# M117E.net
KiCad netlist of a schematic drawn in EAGLE
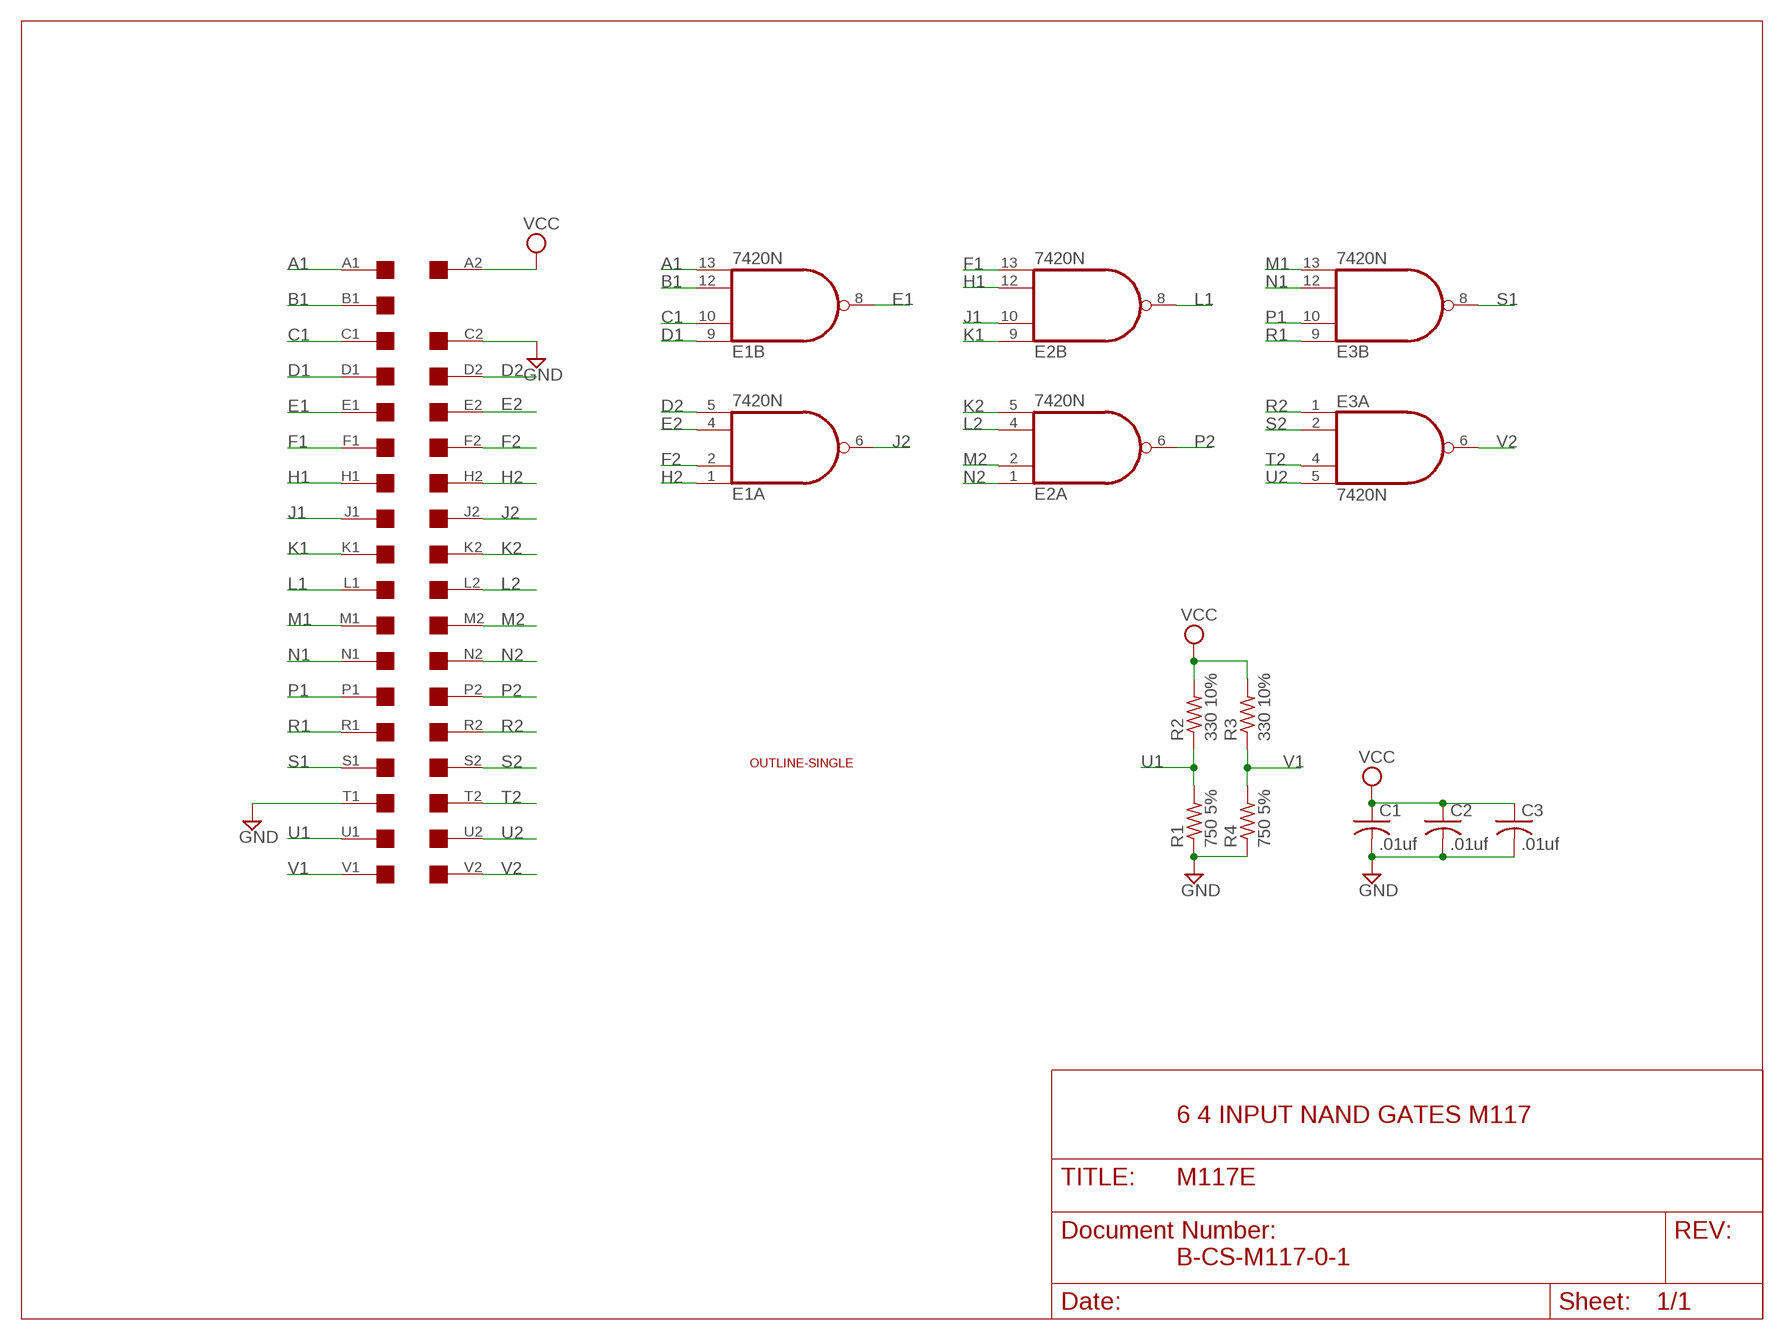
[diagram p0: schematic, sheet 1]

(export (version "E")
  (design (tool "Eeschema 10.0.6"))
  (components
    (comp (ref "C1")
      (value ".01uf")
      (footprint "eagle-import:C050-025X075")
      (libsource (lib "eagle-import") (part "C-US050-025X075"))
    )
    (comp (ref "C2")
      (value ".01uf")
      (footprint "eagle-import:C050-025X075")
      (libsource (lib "eagle-import") (part "C-US050-025X075"))
    )
    (comp (ref "C3")
      (value ".01uf")
      (footprint "eagle-import:C050-025X075")
      (libsource (lib "eagle-import") (part "C-US050-025X075"))
    )
    (comp (ref "E1")
      (value "7420N")
      (footprint "eagle-import:DIL14")
      (libsource (lib "eagle-import") (part "7420NS"))
    )
    (comp (ref "E2")
      (value "7420N")
      (footprint "eagle-import:DIL14")
      (libsource (lib "eagle-import") (part "7420NS"))
    )
    (comp (ref "E3")
      (value "7420N")
      (footprint "eagle-import:DIL14")
      (libsource (lib "eagle-import") (part "7420NS"))
    )
    (comp (ref "R1")
      (value "750 5%")
      (footprint "eagle-import:0207_10")
      (libsource (lib "eagle-import") (part "R-US_0207/10"))
    )
    (comp (ref "R2")
      (value "330 10%")
      (footprint "eagle-import:0207_10")
      (libsource (lib "eagle-import") (part "R-US_0207/10"))
    )
    (comp (ref "R3")
      (value "330 10%")
      (footprint "eagle-import:0207_10")
      (libsource (lib "eagle-import") (part "R-US_0207/10"))
    )
    (comp (ref "R4")
      (value "750 5%")
      (footprint "eagle-import:0207_10")
      (libsource (lib "eagle-import") (part "R-US_0207/10"))
    )
    (comp (ref "U$1")
      (value "SINGLE")
      (footprint "eagle-import:EDGE-CON2")
      (libsource (lib "eagle-import") (part "SINGLE"))
    )
    (comp (ref "U$4")
      (value "OUTLINE-SINGLE")
      (footprint "eagle-import:SINGLE")
      (libsource (lib "eagle-import") (part "OUTLINE-SINGLE"))
    )
  )
  (nets
    (net (code "1") (name "/A1") (class "Default")
      (node (ref "E1") (pin "13") (pinfunction "I3_13") (pintype "input"))
      (node (ref "U$1") (pin "A1") (pinfunction "1_A1") (pintype "bidirectional"))
    )
    (net (code "2") (name "/B1") (class "Default")
      (node (ref "E1") (pin "12") (pinfunction "I2_12") (pintype "input"))
      (node (ref "U$1") (pin "B1") (pinfunction "1_B1") (pintype "bidirectional"))
    )
    (net (code "3") (name "/C1") (class "Default")
      (node (ref "E1") (pin "10") (pinfunction "I1_10") (pintype "input"))
      (node (ref "U$1") (pin "C1") (pinfunction "1_C1") (pintype "bidirectional"))
    )
    (net (code "4") (name "/D1") (class "Default")
      (node (ref "E1") (pin "9") (pinfunction "I0_9") (pintype "input"))
      (node (ref "U$1") (pin "D1") (pinfunction "1_D1") (pintype "bidirectional"))
    )
    (net (code "5") (name "/D2") (class "Default")
      (node (ref "E1") (pin "5") (pinfunction "I3_5") (pintype "input"))
      (node (ref "U$1") (pin "D2") (pinfunction "1_D2") (pintype "bidirectional"))
    )
    (net (code "6") (name "/E1") (class "Default")
      (node (ref "E1") (pin "8") (pinfunction "O_8") (pintype "output"))
      (node (ref "U$1") (pin "E1") (pinfunction "1_E1") (pintype "bidirectional"))
    )
    (net (code "7") (name "/E2") (class "Default")
      (node (ref "E1") (pin "4") (pinfunction "I2_4") (pintype "input"))
      (node (ref "U$1") (pin "E2") (pinfunction "1_E2") (pintype "bidirectional"))
    )
    (net (code "8") (name "/F1") (class "Default")
      (node (ref "E2") (pin "13") (pinfunction "I3_13") (pintype "input"))
      (node (ref "U$1") (pin "F1") (pinfunction "1_F1") (pintype "bidirectional"))
    )
    (net (code "9") (name "/F2") (class "Default")
      (node (ref "E1") (pin "2") (pinfunction "I1_2") (pintype "input"))
      (node (ref "U$1") (pin "F2") (pinfunction "1_F2") (pintype "bidirectional"))
    )
    (net (code "10") (name "/H1") (class "Default")
      (node (ref "E2") (pin "12") (pinfunction "I2_12") (pintype "input"))
      (node (ref "U$1") (pin "H1") (pinfunction "1_H1") (pintype "bidirectional"))
    )
    (net (code "11") (name "/H2") (class "Default")
      (node (ref "E1") (pin "1") (pinfunction "I0_1") (pintype "input"))
      (node (ref "U$1") (pin "H2") (pinfunction "1_H2") (pintype "bidirectional"))
    )
    (net (code "12") (name "/J1") (class "Default")
      (node (ref "E2") (pin "10") (pinfunction "I1_10") (pintype "input"))
      (node (ref "U$1") (pin "J1") (pinfunction "1_J1") (pintype "bidirectional"))
    )
    (net (code "13") (name "/J2") (class "Default")
      (node (ref "E1") (pin "6") (pinfunction "O_6") (pintype "output"))
      (node (ref "U$1") (pin "J2") (pinfunction "1_J2") (pintype "bidirectional"))
    )
    (net (code "14") (name "/K1") (class "Default")
      (node (ref "E2") (pin "9") (pinfunction "I0_9") (pintype "input"))
      (node (ref "U$1") (pin "K1") (pinfunction "1_K1") (pintype "bidirectional"))
    )
    (net (code "15") (name "/K2") (class "Default")
      (node (ref "E2") (pin "5") (pinfunction "I3_5") (pintype "input"))
      (node (ref "U$1") (pin "K2") (pinfunction "1_K2") (pintype "bidirectional"))
    )
    (net (code "16") (name "/L1") (class "Default")
      (node (ref "E2") (pin "8") (pinfunction "O_8") (pintype "output"))
      (node (ref "U$1") (pin "L1") (pinfunction "1_L1") (pintype "bidirectional"))
    )
    (net (code "17") (name "/L2") (class "Default")
      (node (ref "E2") (pin "4") (pinfunction "I2_4") (pintype "input"))
      (node (ref "U$1") (pin "L2") (pinfunction "1_L2") (pintype "bidirectional"))
    )
    (net (code "18") (name "/M1") (class "Default")
      (node (ref "E3") (pin "13") (pinfunction "I3_13") (pintype "input"))
      (node (ref "U$1") (pin "M1") (pinfunction "1_M1") (pintype "bidirectional"))
    )
    (net (code "19") (name "/M2") (class "Default")
      (node (ref "E2") (pin "2") (pinfunction "I1_2") (pintype "input"))
      (node (ref "U$1") (pin "M2") (pinfunction "1_M2") (pintype "bidirectional"))
    )
    (net (code "20") (name "/N1") (class "Default")
      (node (ref "E3") (pin "12") (pinfunction "I2_12") (pintype "input"))
      (node (ref "U$1") (pin "N1") (pinfunction "1_N1") (pintype "bidirectional"))
    )
    (net (code "21") (name "/N2") (class "Default")
      (node (ref "E2") (pin "1") (pinfunction "I0_1") (pintype "input"))
      (node (ref "U$1") (pin "N2") (pinfunction "1_N2") (pintype "bidirectional"))
    )
    (net (code "22") (name "/P1") (class "Default")
      (node (ref "E3") (pin "10") (pinfunction "I1_10") (pintype "input"))
      (node (ref "U$1") (pin "P1") (pinfunction "1_P1") (pintype "bidirectional"))
    )
    (net (code "23") (name "/P2") (class "Default")
      (node (ref "E2") (pin "6") (pinfunction "O_6") (pintype "output"))
      (node (ref "U$1") (pin "P2") (pinfunction "1_P2") (pintype "bidirectional"))
    )
    (net (code "24") (name "/R1") (class "Default")
      (node (ref "E3") (pin "9") (pinfunction "I0_9") (pintype "input"))
      (node (ref "U$1") (pin "R1") (pinfunction "1_R1") (pintype "bidirectional"))
    )
    (net (code "25") (name "/R2") (class "Default")
      (node (ref "E3") (pin "1") (pinfunction "I0_1") (pintype "input"))
      (node (ref "U$1") (pin "R2") (pinfunction "1_R2") (pintype "bidirectional"))
    )
    (net (code "26") (name "/S1") (class "Default")
      (node (ref "E3") (pin "8") (pinfunction "O_8") (pintype "output"))
      (node (ref "U$1") (pin "S1") (pinfunction "1_S1") (pintype "bidirectional"))
    )
    (net (code "27") (name "/S2") (class "Default")
      (node (ref "E3") (pin "2") (pinfunction "I1_2") (pintype "input"))
      (node (ref "U$1") (pin "S2") (pinfunction "1_S2") (pintype "bidirectional"))
    )
    (net (code "28") (name "/T2") (class "Default")
      (node (ref "E3") (pin "4") (pinfunction "I2_4") (pintype "input"))
      (node (ref "U$1") (pin "T2") (pinfunction "1_T2") (pintype "bidirectional"))
    )
    (net (code "29") (name "/U1") (class "Default")
      (node (ref "R1") (pin "2") (pinfunction "2_2") (pintype "passive"))
      (node (ref "R2") (pin "1") (pinfunction "1_1") (pintype "passive"))
      (node (ref "U$1") (pin "U1") (pinfunction "1_U1") (pintype "bidirectional"))
    )
    (net (code "30") (name "/U2") (class "Default")
      (node (ref "E3") (pin "5") (pinfunction "I3_5") (pintype "input"))
      (node (ref "U$1") (pin "U2") (pinfunction "1_U2") (pintype "bidirectional"))
    )
    (net (code "31") (name "/V1") (class "Default")
      (node (ref "R3") (pin "1") (pinfunction "1_1") (pintype "passive"))
      (node (ref "R4") (pin "2") (pinfunction "2_2") (pintype "passive"))
      (node (ref "U$1") (pin "V1") (pinfunction "1_V1") (pintype "bidirectional"))
    )
    (net (code "32") (name "/V2") (class "Default")
      (node (ref "E3") (pin "6") (pinfunction "O_6") (pintype "output"))
      (node (ref "U$1") (pin "V2") (pinfunction "1_V2") (pintype "bidirectional"))
    )
    (net (code "33") (name "GND") (class "Default")
      (node (ref "C1") (pin "2") (pinfunction "2_2") (pintype "passive"))
      (node (ref "C2") (pin "2") (pinfunction "2_2") (pintype "passive"))
      (node (ref "C3") (pin "2") (pinfunction "2_2") (pintype "passive"))
      (node (ref "R1") (pin "1") (pinfunction "1_1") (pintype "passive"))
      (node (ref "R4") (pin "1") (pinfunction "1_1") (pintype "passive"))
      (node (ref "U$1") (pin "C2") (pinfunction "1_C2") (pintype "bidirectional"))
      (node (ref "U$1") (pin "T1") (pinfunction "1_T1") (pintype "bidirectional"))
    )
    (net (code "34") (name "VCC") (class "Default")
      (node (ref "C1") (pin "1") (pinfunction "1_1") (pintype "passive"))
      (node (ref "C2") (pin "1") (pinfunction "1_1") (pintype "passive"))
      (node (ref "C3") (pin "1") (pinfunction "1_1") (pintype "passive"))
      (node (ref "R2") (pin "2") (pinfunction "2_2") (pintype "passive"))
      (node (ref "R3") (pin "2") (pinfunction "2_2") (pintype "passive"))
      (node (ref "U$1") (pin "A2") (pinfunction "1_A2") (pintype "bidirectional"))
    )
  )
)
